# LampPCB.net
KiCad netlist of a schematic drawn in EasyEDA Pro
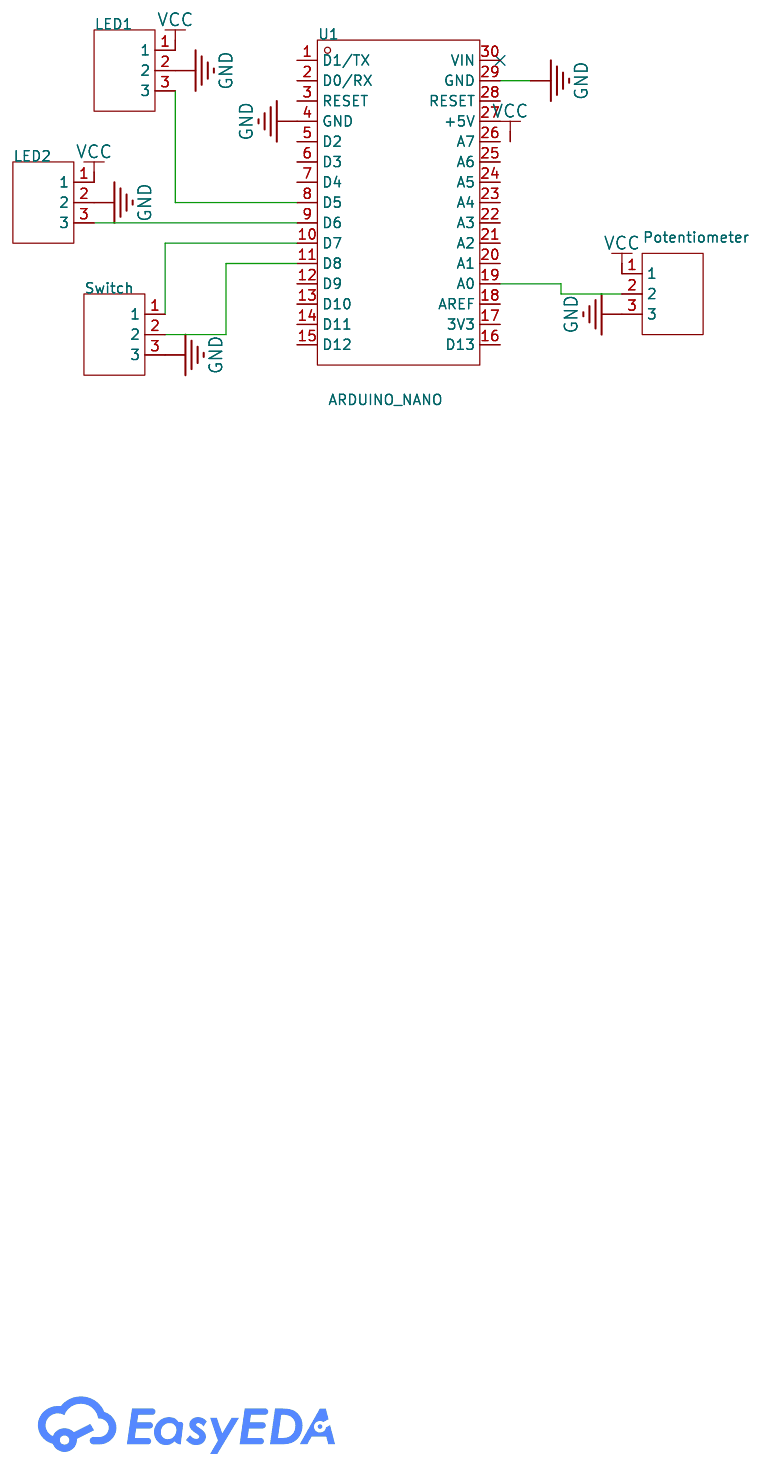
[diagram p0: schematic sheet]

(export (version "E")
  (design (tool "Eeschema 10.0.6"))
  (components
    (comp (ref "LED1")
      (value "RE-H032TD-1130")
      (footprint "easyedapro:HDR-TH_3P-P2.54-V-M-1")
      (fields (field (name "Manufacturer") "JST"))
      (libsource (lib "easyedapro") (part "RE-H032TD-1130"))
    )
    (comp (ref "LED2")
      (value "RE-H032TD-1130")
      (footprint "easyedapro:HDR-TH_3P-P2.54-V-M-1")
      (fields (field (name "Manufacturer") "JST"))
      (libsource (lib "easyedapro") (part "RE-H032TD-1130"))
    )
    (comp (ref "Potentiometer")
      (value "RE-H032TD-1130")
      (footprint "easyedapro:HDR-TH_3P-P2.54-V-M-1")
      (fields (field (name "Manufacturer") "JST"))
      (libsource (lib "easyedapro") (part "RE-H032TD-1130"))
    )
    (comp (ref "Switch")
      (value "RE-H032TD-1130")
      (footprint "easyedapro:HDR-TH_3P-P2.54-V-M-1")
      (fields (field (name "Manufacturer") "JST"))
      (libsource (lib "easyedapro") (part "RE-H032TD-1130"))
    )
    (comp (ref "U1")
      (value "ARDUINO_NANO")
      (footprint "easyedapro:ARDUINO_NANO_SMD_V3")
      (libsource (lib "easyedapro") (part "ARDUINO_NANO_SMD_V3"))
    )
  )
  (nets
    (net (code "1") (name "GND") (class "Default")
      (node (ref "LED1") (pin "2") (pinfunction "2_2") (pintype "unspecified"))
      (node (ref "LED2") (pin "2") (pinfunction "2_2") (pintype "unspecified"))
      (node (ref "Potentiometer") (pin "3") (pinfunction "3_3") (pintype "unspecified"))
      (node (ref "Switch") (pin "3") (pinfunction "3_3") (pintype "unspecified"))
      (node (ref "U1") (pin "29") (pinfunction "GND_29") (pintype "input"))
      (node (ref "U1") (pin "4") (pinfunction "GND_4") (pintype "input"))
    )
    (net (code "2") (name "Net-(U1-A0)") (class "Default")
      (node (ref "Potentiometer") (pin "2") (pinfunction "2_2") (pintype "unspecified"))
      (node (ref "U1") (pin "19") (pinfunction "A0_19") (pintype "input"))
    )
    (net (code "3") (name "Net-(U1-D5)") (class "Default")
      (node (ref "LED1") (pin "3") (pinfunction "3_3") (pintype "unspecified"))
      (node (ref "U1") (pin "8") (pinfunction "D5_8") (pintype "input"))
    )
    (net (code "4") (name "Net-(U1-D6)") (class "Default")
      (node (ref "LED2") (pin "3") (pinfunction "3_3") (pintype "unspecified"))
      (node (ref "U1") (pin "9") (pinfunction "D6_9") (pintype "input"))
    )
    (net (code "5") (name "Net-(U1-D7)") (class "Default")
      (node (ref "Switch") (pin "1") (pinfunction "1_1") (pintype "unspecified"))
      (node (ref "U1") (pin "10") (pinfunction "D7_10") (pintype "input"))
    )
    (net (code "6") (name "Net-(U1-D8)") (class "Default")
      (node (ref "Switch") (pin "2") (pinfunction "2_2") (pintype "unspecified"))
      (node (ref "U1") (pin "11") (pinfunction "D8_11") (pintype "input"))
    )
    (net (code "7") (name "VCC") (class "Default")
      (node (ref "LED1") (pin "1") (pinfunction "1_1") (pintype "unspecified"))
      (node (ref "LED2") (pin "1") (pinfunction "1_1") (pintype "unspecified"))
      (node (ref "Potentiometer") (pin "1") (pinfunction "1_1") (pintype "unspecified"))
    )
    (net (code "8") (name "unconnected-(U1-+5V-Pad27)") (class "Default")
      (node (ref "U1") (pin "27") (pinfunction "+5V_27") (pintype "input"))
    )
    (net (code "9") (name "unconnected-(U1-3V3-Pad17)") (class "Default")
      (node (ref "U1") (pin "17") (pinfunction "3V3_17") (pintype "input"))
    )
    (net (code "10") (name "unconnected-(U1-A1-Pad20)") (class "Default")
      (node (ref "U1") (pin "20") (pinfunction "A1_20") (pintype "input"))
    )
    (net (code "11") (name "unconnected-(U1-A2-Pad21)") (class "Default")
      (node (ref "U1") (pin "21") (pinfunction "A2_21") (pintype "input"))
    )
    (net (code "12") (name "unconnected-(U1-A3-Pad22)") (class "Default")
      (node (ref "U1") (pin "22") (pinfunction "A3_22") (pintype "input"))
    )
    (net (code "13") (name "unconnected-(U1-A4-Pad23)") (class "Default")
      (node (ref "U1") (pin "23") (pinfunction "A4_23") (pintype "input"))
    )
    (net (code "14") (name "unconnected-(U1-A5-Pad24)") (class "Default")
      (node (ref "U1") (pin "24") (pinfunction "A5_24") (pintype "input"))
    )
    (net (code "15") (name "unconnected-(U1-A6-Pad25)") (class "Default")
      (node (ref "U1") (pin "25") (pinfunction "A6_25") (pintype "input"))
    )
    (net (code "16") (name "unconnected-(U1-A7-Pad26)") (class "Default")
      (node (ref "U1") (pin "26") (pinfunction "A7_26") (pintype "input"))
    )
    (net (code "17") (name "unconnected-(U1-AREF-Pad18)") (class "Default")
      (node (ref "U1") (pin "18") (pinfunction "AREF_18") (pintype "input"))
    )
    (net (code "18") (name "unconnected-(U1-D0{slash}RX-Pad2)") (class "Default")
      (node (ref "U1") (pin "2") (pinfunction "D0/RX_2") (pintype "input"))
    )
    (net (code "19") (name "unconnected-(U1-D1{slash}TX-Pad1)") (class "Default")
      (node (ref "U1") (pin "1") (pinfunction "D1/TX_1") (pintype "input"))
    )
    (net (code "20") (name "unconnected-(U1-D2-Pad5)") (class "Default")
      (node (ref "U1") (pin "5") (pinfunction "D2_5") (pintype "input"))
    )
    (net (code "21") (name "unconnected-(U1-D3-Pad6)") (class "Default")
      (node (ref "U1") (pin "6") (pinfunction "D3_6") (pintype "input"))
    )
    (net (code "22") (name "unconnected-(U1-D4-Pad7)") (class "Default")
      (node (ref "U1") (pin "7") (pinfunction "D4_7") (pintype "input"))
    )
    (net (code "23") (name "unconnected-(U1-D9-Pad12)") (class "Default")
      (node (ref "U1") (pin "12") (pinfunction "D9_12") (pintype "input"))
    )
    (net (code "24") (name "unconnected-(U1-D10-Pad13)") (class "Default")
      (node (ref "U1") (pin "13") (pinfunction "D10_13") (pintype "input"))
    )
    (net (code "25") (name "unconnected-(U1-D11-Pad14)") (class "Default")
      (node (ref "U1") (pin "14") (pinfunction "D11_14") (pintype "input"))
    )
    (net (code "26") (name "unconnected-(U1-D12-Pad15)") (class "Default")
      (node (ref "U1") (pin "15") (pinfunction "D12_15") (pintype "input"))
    )
    (net (code "27") (name "unconnected-(U1-D13-Pad16)") (class "Default")
      (node (ref "U1") (pin "16") (pinfunction "D13_16") (pintype "input"))
    )
    (net (code "28") (name "unconnected-(U1-RESET-Pad3)") (class "Default")
      (node (ref "U1") (pin "3") (pinfunction "RESET_3") (pintype "input"))
    )
    (net (code "29") (name "unconnected-(U1-RESET-Pad28)") (class "Default")
      (node (ref "U1") (pin "28") (pinfunction "RESET_28") (pintype "input"))
    )
    (net (code "30") (name "unconnected-(U1-VIN-Pad30)") (class "Default")
      (node (ref "U1") (pin "30") (pinfunction "VIN_30") (pintype "input+no_connect"))
    )
  )
)
